# PWR_CTRL.net
KiCad netlist of a schematic drawn in Altium Designer
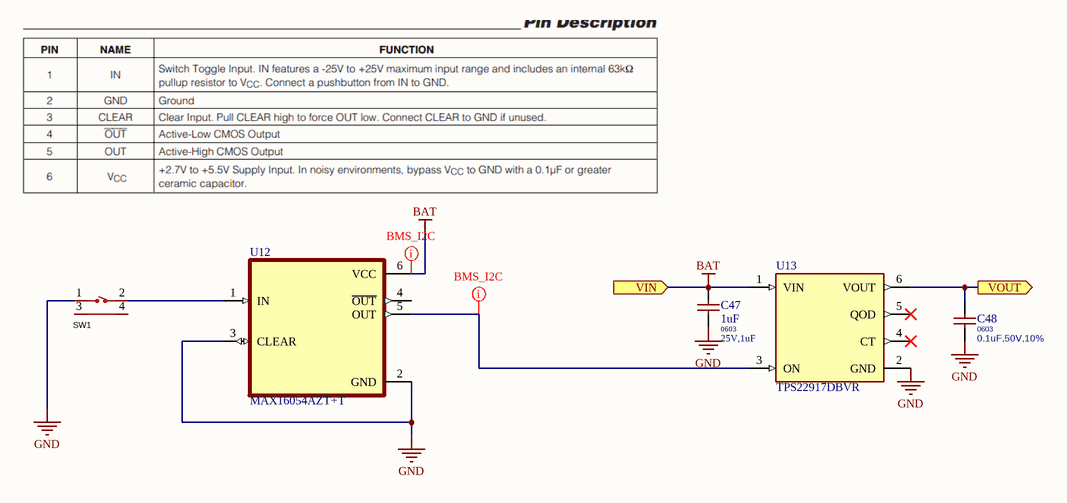
[diagram p0: PWR_CTRL.SchDoc]

(export (version "E")
  (design (tool "Eeschema 10.0.6"))
  (components
    (comp (ref "C47")
      (value "1uF")
      (footprint "CAPC1608X90N")
      (description "25V 1uF X7R ±10% 0603 Multilayer Ceramic Capacitors MLCC - SMD/SMT ROHS")
      (fields
        (field (name "MANUFACTURER") "FH (Guangdong Fenghua Advanced Tech)")
        (field (name "MPN") "0603B105K250NT")
        (field (name "PACKAGE") "0603")
        (field (name "ALTIUM_VALUE") "25V,1uF")
      )
      (libsource (lib "RCL") (part "0603B105K250NT"))
    )
    (comp (ref "C48")
      (value "0.1uF,50V,10%")
      (footprint "C0603")
      (description "CAP CER 0.1UF 50V X7R 0603")
      (fields
        (field (name "MANUFACTURER") "Murata Electronics")
        (field (name "MPN") "GCM188R71H104KA57J")
        (field (name "PACKAGE") "0603")
      )
      (libsource (lib "RCL") (part "GCM188R71H104KA57J"))
    )
    (comp (ref "SW1")
      (value "~")
      (footprint "SW-TH_4P-L7.5-W8.0-P4.50")
      (fields (field (name "MANUFACTURER") "HCTL") (field (name "MPN") "TC-6615-8-260G"))
      (libsource (lib "connector_button") (part "TC-6615-8-260G"))
    )
    (comp (ref "U12")
      (value "MAX16054AZT+T")
      (footprint "SOT95P275X110-6N")
      (description "On/Off Controller with Debounce and Â±15kV ESD Protection")
      (fields (field (name "MF") "Analog Devices"))
      (libsource (lib "IC") (part "MAX16054AZT+T"))
    )
    (comp (ref "U13")
      (value "TPS22917DBVR")
      (footprint "SOT95P280X145-6N")
      (description "5.5-V, 2-A, 80-mÎ© , 10-nA leakage load switch adj. rise time and adj output discharge")
      (fields (field (name "MF") "Texas Instruments"))
      (libsource (lib "IC") (part "TPS22917DBVR"))
    )
  )
  (nets
    (net (code "1") (name "/VOUT") (class "Default")
      (node (ref "C48") (pin "2") (pinfunction "2_2") (pintype "passive"))
      (node (ref "U13") (pin "6") (pinfunction "VOUT_6") (pintype "output"))
    )
    (net (code "2") (name "BAT") (class "Default")
      (node (ref "C47") (pin "2") (pinfunction "2_2") (pintype "passive"))
      (node (ref "U12") (pin "6") (pinfunction "VCC_6") (pintype "power_in"))
      (node (ref "U13") (pin "1") (pinfunction "VIN_1") (pintype "input"))
    )
    (net (code "3") (name "GND") (class "Default")
      (node (ref "C47") (pin "1") (pinfunction "1_1") (pintype "passive"))
      (node (ref "C48") (pin "1") (pinfunction "1_1") (pintype "passive"))
      (node (ref "SW1") (pin "1") (pinfunction "1_1") (pintype "passive"))
      (node (ref "U12") (pin "2") (pinfunction "GND_2") (pintype "power_in"))
      (node (ref "U12") (pin "3") (pinfunction "CLEAR_3") (pintype "bidirectional"))
      (node (ref "U13") (pin "2") (pinfunction "GND_2") (pintype "power_in"))
    )
    (net (code "4") (name "Net-(U12-IN)") (class "Default")
      (node (ref "SW1") (pin "2") (pinfunction "2_2") (pintype "passive"))
      (node (ref "U12") (pin "1") (pinfunction "IN_1") (pintype "input"))
    )
    (net (code "5") (name "Net-(U12-OUT)") (class "Default")
      (node (ref "U12") (pin "5") (pinfunction "OUT_5") (pintype "output"))
      (node (ref "U13") (pin "3") (pinfunction "ON_3") (pintype "input"))
    )
    (net (code "6") (name "unconnected-(SW1-Pad3)") (class "Default")
      (node (ref "SW1") (pin "3") (pinfunction "3_3") (pintype "passive"))
    )
    (net (code "7") (name "unconnected-(SW1-Pad4)") (class "Default")
      (node (ref "SW1") (pin "4") (pinfunction "4_4") (pintype "passive"))
    )
    (net (code "8") (name "unconnected-(U12-~{OUT}-Pad4)") (class "Default")
      (node (ref "U12") (pin "4") (pinfunction "~{OUT}_4") (pintype "output"))
    )
    (net (code "9") (name "unconnected-(U13-CT-Pad4)") (class "Default")
      (node (ref "U13") (pin "4") (pinfunction "CT_4") (pintype "output+no_connect"))
    )
    (net (code "10") (name "unconnected-(U13-QOD-Pad5)") (class "Default")
      (node (ref "U13") (pin "5") (pinfunction "QOD_5") (pintype "output+no_connect"))
    )
  )
)
